# Capstone_V7.net
KiCad netlist of a schematic drawn in EAGLE
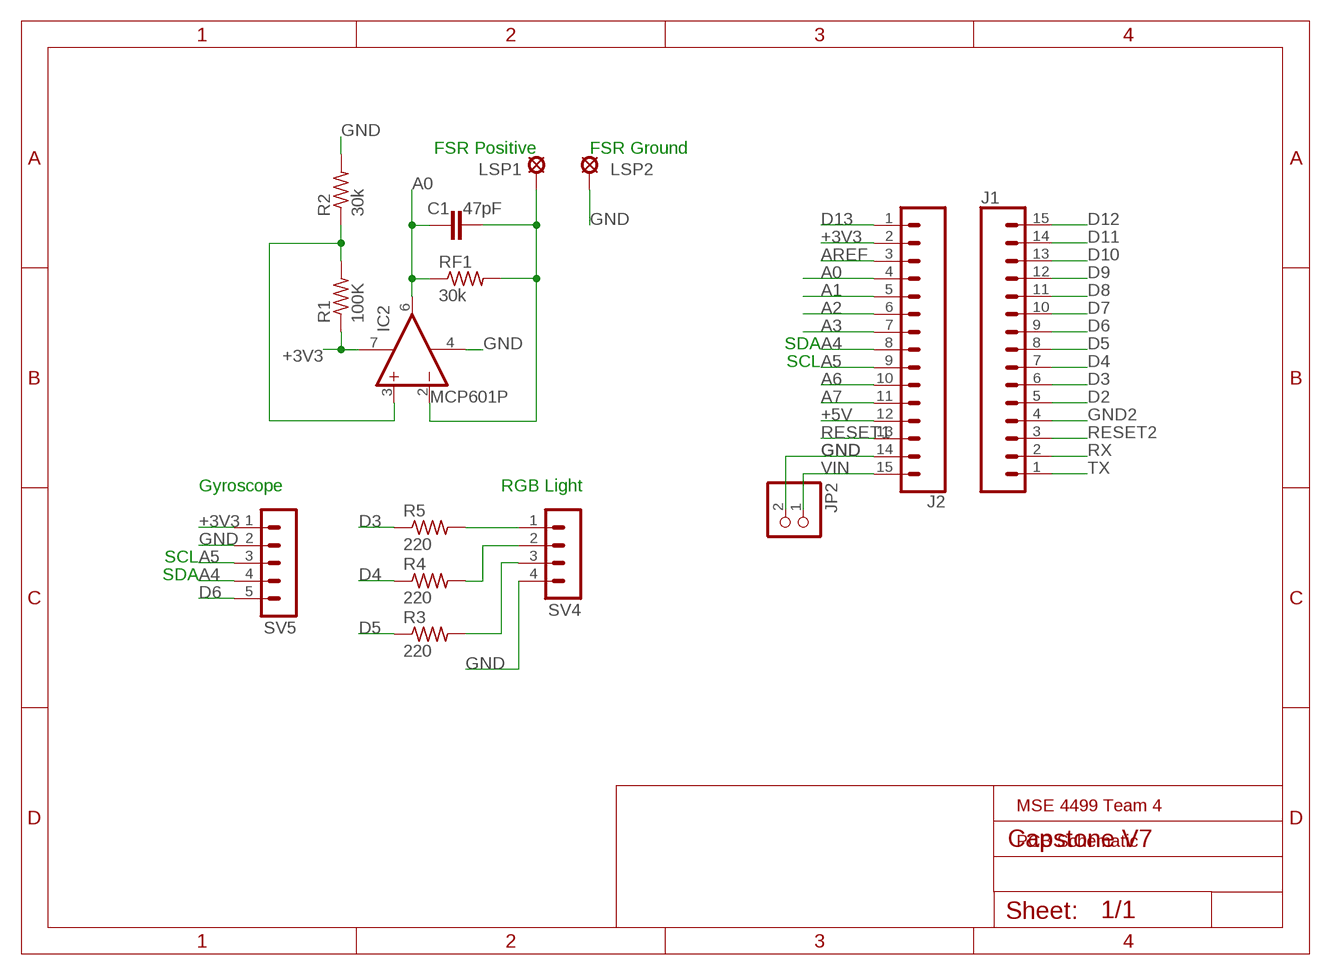
[diagram p0: schematic, sheet 1]

(export (version "E")
  (design (tool "Eeschema 10.0.6"))
  (components
    (comp (ref "C1")
      (value "47pF")
      (footprint "eagle-import:C2.5-3")
      (libsource (lib "eagle-import") (part "C2,5-3"))
    )
    (comp (ref "IC2")
      (value "MCP601P")
      (footprint "eagle-import:DIL08")
      (libsource (lib "eagle-import") (part "MCP601P"))
    )
    (comp (ref "J1")
      (value "CONN_15")
      (footprint "eagle-import:1X15")
      (libsource (lib "eagle-import") (part "CONN_15"))
    )
    (comp (ref "J2")
      (value "CONN_15")
      (footprint "eagle-import:1X15")
      (libsource (lib "eagle-import") (part "CONN_15"))
    )
    (comp (ref "JP2")
      (value "PINHD-1X2")
      (footprint "eagle-import:1X02")
      (libsource (lib "eagle-import") (part "PINHD-1X2"))
    )
    (comp (ref "LSP1")
      (value "LSP10")
      (footprint "eagle-import:LSP10")
      (libsource (lib "eagle-import") (part "LSP10"))
    )
    (comp (ref "LSP2")
      (value "LSP10")
      (footprint "eagle-import:LSP10")
      (libsource (lib "eagle-import") (part "LSP10"))
    )
    (comp (ref "R1")
      (value "100K")
      (footprint "eagle-import:0204_7")
      (libsource (lib "eagle-import") (part "R-US_0204/7"))
    )
    (comp (ref "R2")
      (value "30k")
      (footprint "eagle-import:0204_7")
      (libsource (lib "eagle-import") (part "R-US_0204/7"))
    )
    (comp (ref "R3")
      (value "220")
      (footprint "eagle-import:0204_7")
      (libsource (lib "eagle-import") (part "R-US_0204/7"))
    )
    (comp (ref "R4")
      (value "220")
      (footprint "eagle-import:0204_7")
      (libsource (lib "eagle-import") (part "R-US_0204/7"))
    )
    (comp (ref "R5")
      (value "220")
      (footprint "eagle-import:0204_7")
      (libsource (lib "eagle-import") (part "R-US_0204/7"))
    )
    (comp (ref "RF1")
      (value "30k")
      (footprint "eagle-import:0204_7")
      (libsource (lib "eagle-import") (part "R-US_0204/7"))
    )
    (comp (ref "SV4")
      (value "MA04-1")
      (footprint "eagle-import:MA04-1")
      (libsource (lib "eagle-import") (part "MA04-1"))
    )
    (comp (ref "SV5")
      (value "MA05-1")
      (footprint "eagle-import:MA05-1")
      (libsource (lib "eagle-import") (part "MA05-1"))
    )
  )
  (nets
    (net (code "1") (name "/+3V3") (class "Default")
      (node (ref "IC2") (pin "7") (pinfunction "V+_7") (pintype "power_in"))
      (node (ref "J2") (pin "2") (pinfunction "2_2") (pintype "passive"))
      (node (ref "R1") (pin "1") (pinfunction "1_1") (pintype "passive"))
      (node (ref "SV5") (pin "1") (pinfunction "1_1") (pintype "passive"))
    )
    (net (code "2") (name "/+5V") (class "Default")
      (node (ref "J2") (pin "12") (pinfunction "12_12") (pintype "passive"))
    )
    (net (code "3") (name "/A0") (class "Default")
      (node (ref "C1") (pin "1") (pinfunction "1_1") (pintype "passive"))
      (node (ref "IC2") (pin "6") (pinfunction "OUT_6") (pintype "output"))
      (node (ref "J2") (pin "4") (pinfunction "4_4") (pintype "passive"))
      (node (ref "RF1") (pin "1") (pinfunction "1_1") (pintype "passive"))
    )
    (net (code "4") (name "/A1") (class "Default")
      (node (ref "J2") (pin "5") (pinfunction "5_5") (pintype "passive"))
    )
    (net (code "5") (name "/A2") (class "Default")
      (node (ref "J2") (pin "6") (pinfunction "6_6") (pintype "passive"))
    )
    (net (code "6") (name "/A3") (class "Default")
      (node (ref "J2") (pin "7") (pinfunction "7_7") (pintype "passive"))
    )
    (net (code "7") (name "/A4") (class "Default")
      (node (ref "J2") (pin "8") (pinfunction "8_8") (pintype "passive"))
      (node (ref "SV5") (pin "4") (pinfunction "4_4") (pintype "passive"))
    )
    (net (code "8") (name "/A5") (class "Default")
      (node (ref "J2") (pin "9") (pinfunction "9_9") (pintype "passive"))
      (node (ref "SV5") (pin "3") (pinfunction "3_3") (pintype "passive"))
    )
    (net (code "9") (name "/A6") (class "Default")
      (node (ref "J2") (pin "10") (pinfunction "10_10") (pintype "passive"))
    )
    (net (code "10") (name "/A7") (class "Default")
      (node (ref "J2") (pin "11") (pinfunction "11_11") (pintype "passive"))
    )
    (net (code "11") (name "/AREF") (class "Default")
      (node (ref "J2") (pin "3") (pinfunction "3_3") (pintype "passive"))
    )
    (net (code "12") (name "/D2") (class "Default")
      (node (ref "J1") (pin "5") (pinfunction "5_5") (pintype "passive"))
    )
    (net (code "13") (name "/D3") (class "Default")
      (node (ref "J1") (pin "6") (pinfunction "6_6") (pintype "passive"))
      (node (ref "R5") (pin "1") (pinfunction "1_1") (pintype "passive"))
    )
    (net (code "14") (name "/D4") (class "Default")
      (node (ref "J1") (pin "7") (pinfunction "7_7") (pintype "passive"))
      (node (ref "R4") (pin "1") (pinfunction "1_1") (pintype "passive"))
    )
    (net (code "15") (name "/D5") (class "Default")
      (node (ref "J1") (pin "8") (pinfunction "8_8") (pintype "passive"))
      (node (ref "R3") (pin "1") (pinfunction "1_1") (pintype "passive"))
    )
    (net (code "16") (name "/D6") (class "Default")
      (node (ref "J1") (pin "9") (pinfunction "9_9") (pintype "passive"))
      (node (ref "SV5") (pin "5") (pinfunction "5_5") (pintype "passive"))
    )
    (net (code "17") (name "/D7") (class "Default")
      (node (ref "J1") (pin "10") (pinfunction "10_10") (pintype "passive"))
    )
    (net (code "18") (name "/D8") (class "Default")
      (node (ref "J1") (pin "11") (pinfunction "11_11") (pintype "passive"))
    )
    (net (code "19") (name "/D9") (class "Default")
      (node (ref "J1") (pin "12") (pinfunction "12_12") (pintype "passive"))
    )
    (net (code "20") (name "/D10") (class "Default")
      (node (ref "J1") (pin "13") (pinfunction "13_13") (pintype "passive"))
    )
    (net (code "21") (name "/D11") (class "Default")
      (node (ref "J1") (pin "14") (pinfunction "14_14") (pintype "passive"))
    )
    (net (code "22") (name "/D12") (class "Default")
      (node (ref "J1") (pin "15") (pinfunction "15_15") (pintype "passive"))
    )
    (net (code "23") (name "/D13") (class "Default")
      (node (ref "J2") (pin "1") (pinfunction "1_1") (pintype "passive"))
    )
    (net (code "24") (name "/GND") (class "Default")
      (node (ref "IC2") (pin "4") (pinfunction "V-_4") (pintype "power_in"))
      (node (ref "J2") (pin "14") (pinfunction "14_14") (pintype "passive"))
      (node (ref "JP2") (pin "2") (pinfunction "2_2") (pintype "passive"))
      (node (ref "LSP2") (pin "MP") (pinfunction "MP_MP") (pintype "passive"))
      (node (ref "R2") (pin "2") (pinfunction "2_2") (pintype "passive"))
      (node (ref "SV4") (pin "4") (pinfunction "4_4") (pintype "passive"))
      (node (ref "SV5") (pin "2") (pinfunction "2_2") (pintype "passive"))
    )
    (net (code "25") (name "/GND2") (class "Default")
      (node (ref "J1") (pin "4") (pinfunction "4_4") (pintype "passive"))
    )
    (net (code "26") (name "/RESET1") (class "Default")
      (node (ref "J2") (pin "13") (pinfunction "13_13") (pintype "passive"))
    )
    (net (code "27") (name "/RESET2") (class "Default")
      (node (ref "J1") (pin "3") (pinfunction "3_3") (pintype "passive"))
    )
    (net (code "28") (name "/RX") (class "Default")
      (node (ref "J1") (pin "2") (pinfunction "2_2") (pintype "passive"))
    )
    (net (code "29") (name "/TX") (class "Default")
      (node (ref "J1") (pin "1") (pinfunction "1_1") (pintype "passive"))
    )
    (net (code "30") (name "/VIN") (class "Default")
      (node (ref "J2") (pin "15") (pinfunction "15_15") (pintype "passive"))
      (node (ref "JP2") (pin "1") (pinfunction "1_1") (pintype "passive"))
    )
    (net (code "31") (name "Net-(IC2-+IN)") (class "Default")
      (node (ref "IC2") (pin "3") (pinfunction "+IN_3") (pintype "input"))
      (node (ref "R1") (pin "2") (pinfunction "2_2") (pintype "passive"))
      (node (ref "R2") (pin "1") (pinfunction "1_1") (pintype "passive"))
    )
    (net (code "32") (name "Net-(IC2--IN)") (class "Default")
      (node (ref "C1") (pin "2") (pinfunction "2_2") (pintype "passive"))
      (node (ref "IC2") (pin "2") (pinfunction "-IN_2") (pintype "input"))
      (node (ref "LSP1") (pin "MP") (pinfunction "MP_MP") (pintype "passive"))
      (node (ref "RF1") (pin "2") (pinfunction "2_2") (pintype "passive"))
    )
    (net (code "33") (name "Net-(R3-Pad2)") (class "Default")
      (node (ref "R3") (pin "2") (pinfunction "2_2") (pintype "passive"))
      (node (ref "SV4") (pin "3") (pinfunction "3_3") (pintype "passive"))
    )
    (net (code "34") (name "Net-(R4-Pad2)") (class "Default")
      (node (ref "R4") (pin "2") (pinfunction "2_2") (pintype "passive"))
      (node (ref "SV4") (pin "2") (pinfunction "2_2") (pintype "passive"))
    )
    (net (code "35") (name "Net-(R5-Pad2)") (class "Default")
      (node (ref "R5") (pin "2") (pinfunction "2_2") (pintype "passive"))
      (node (ref "SV4") (pin "1") (pinfunction "1_1") (pintype "passive"))
    )
  )
)
